# Switch.net
KiCad netlist of a schematic drawn in Altium Designer
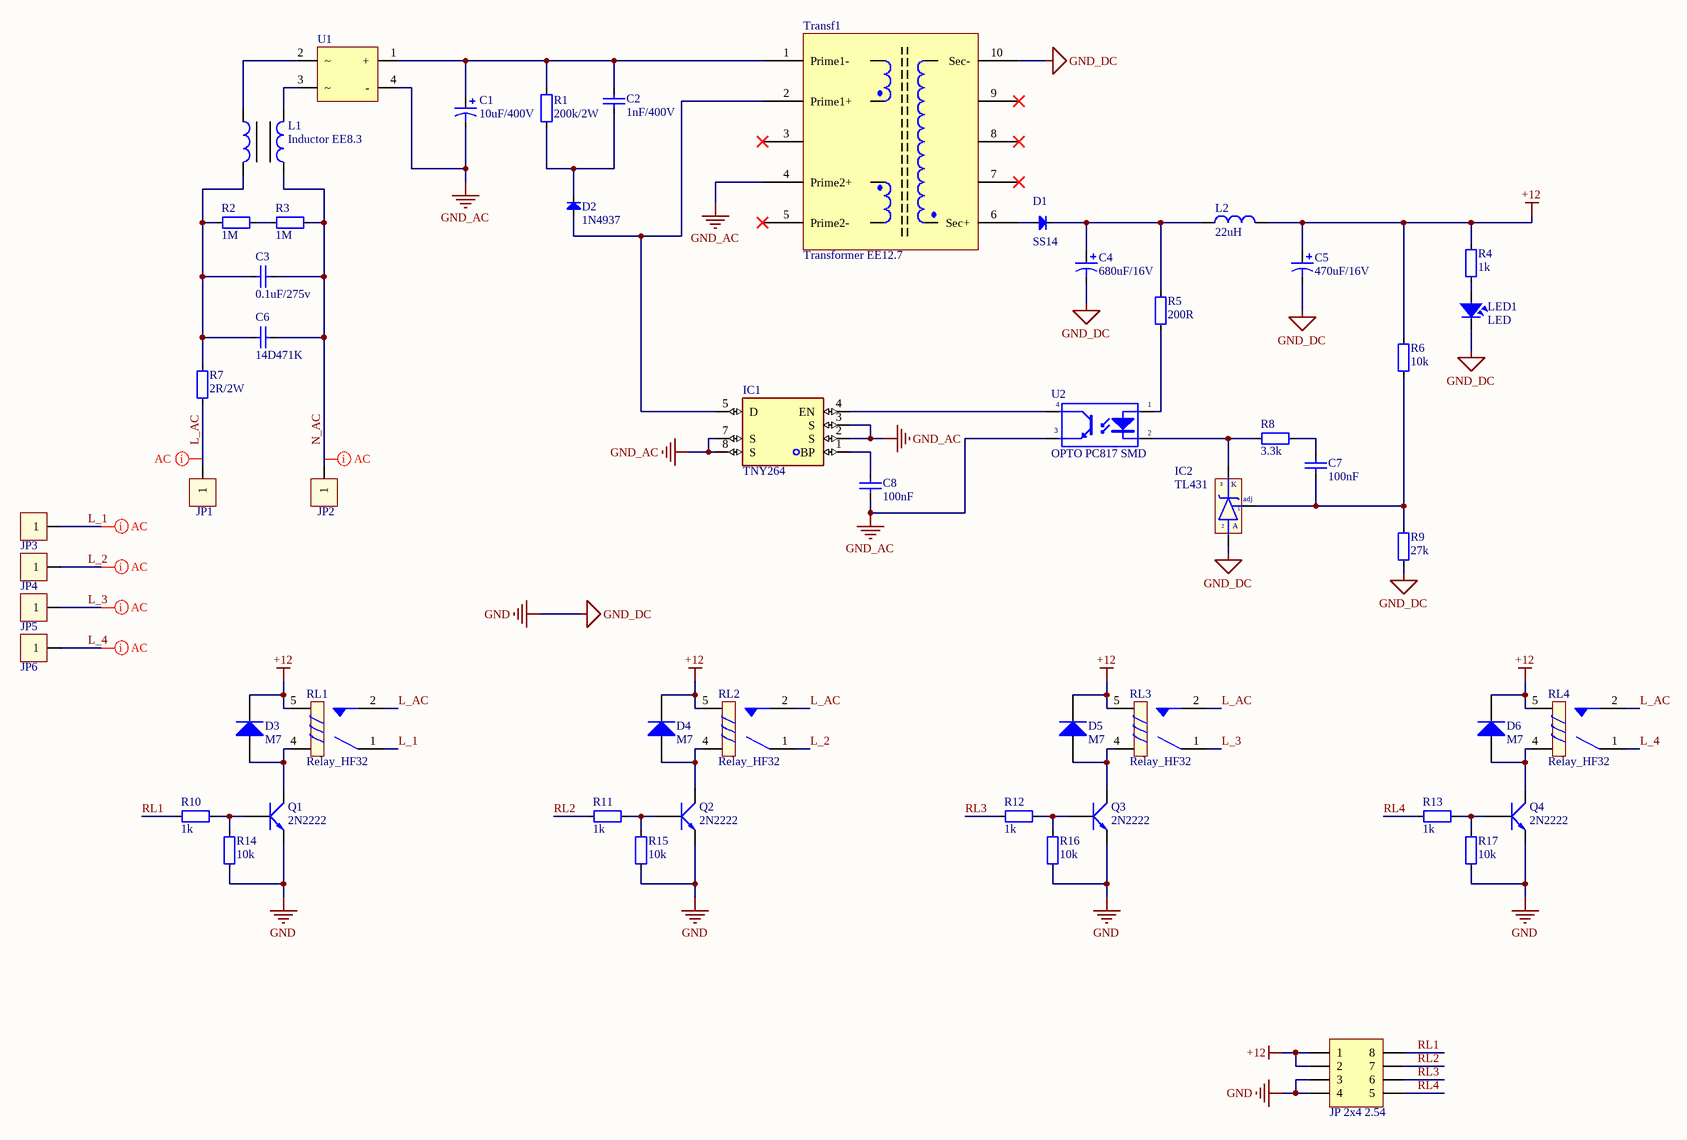
[diagram p0: Switch.SchDoc]

(export (version "E")
  (design (tool "Eeschema 10.0.6"))
  (components
    (comp (ref "C1")
      (value "10uF/400V")
      (footprint "C10mm")
      (description "Polarized Capacitor (Axial)")
      (fields (field (name "PUBLISHER") "Altium Limited"))
      (libsource (lib "My Library") (part "Cap Pol"))
    )
    (comp (ref "C2")
      (value "1nF/400V")
      (footprint "103/2KV")
      (description "CAP CERAMIC")
      (fields (field (name "PUBLISHER") "Altium Limited"))
      (libsource (lib "My Library") (part "Cap2KV"))
    )
    (comp (ref "C3")
      (value "0.1uF/275v")
      (footprint "Cap AC filter")
      (description "Tụ lọc nguồn AC 0.1uf 275v 10mm")
      (libsource (lib "My Library") (part "Cap AC filter"))
    )
    (comp (ref "C4")
      (value "680uF/16V")
      (footprint "C8mm")
      (description "Polarized Capacitor (Axial)")
      (fields (field (name "PUBLISHER") "Altium Limited"))
      (libsource (lib "My Library") (part "Cap Pol"))
    )
    (comp (ref "C5")
      (value "470uF/16V")
      (footprint "C8mm")
      (description "Polarized Capacitor (Axial)")
      (fields (field (name "PUBLISHER") "Altium Limited"))
      (libsource (lib "My Library") (part "Cap Pol"))
    )
    (comp (ref "C6")
      (value "14D471K")
      (footprint "103/2KV")
      (description "Capacitor Ceramic 2KV")
      (fields (field (name "PUBLISHER") "Altium Limited"))
      (libsource (lib "My Library") (part "Cap2KV"))
    )
    (comp (ref "C7")
      (value "100nF")
      (footprint "CAP_0603")
      (description "Capacitor")
      (fields (field (name "PUBLISHER") "Altium Limited"))
      (libsource (lib "My Library") (part "CapSMD"))
    )
    (comp (ref "C8")
      (value "100nF")
      (footprint "CAP_0603")
      (description "Capacitor")
      (fields (field (name "PUBLISHER") "Altium Limited"))
      (libsource (lib "My Library") (part "CapSMD"))
    )
    (comp (ref "D1")
      (value "SS14")
      (footprint "DO-214AC(SMA)")
      (description "Diode Schottky\r\n1N5819")
      (fields (field (name "PUBLISHER") "Altium Limited"))
      (libsource (lib "My Library") (part "Diode SMD"))
    )
    (comp (ref "D2")
      (value "1N4937")
      (footprint "DIO-1AN")
      (description "Diode Schottky\r\n1N4937")
      (fields (field (name "PUBLISHER") "Altium Limited"))
      (libsource (lib "My Library") (part "Diode SMD"))
    )
    (comp (ref "D3")
      (value "M7")
      (footprint "DIODE SMA")
      (description "Dán")
      (libsource (lib "Altium_Lib_by_KhueNguyenCreator") (part "Diode M7 ( 4007 )"))
    )
    (comp (ref "D4")
      (value "M7")
      (footprint "DIODE SMA")
      (description "Dán")
      (libsource (lib "Altium_Lib_by_KhueNguyenCreator") (part "Diode M7 ( 4007 )"))
    )
    (comp (ref "D5")
      (value "M7")
      (footprint "DIODE SMA")
      (description "Dán")
      (libsource (lib "Altium_Lib_by_KhueNguyenCreator") (part "Diode M7 ( 4007 )"))
    )
    (comp (ref "D6")
      (value "M7")
      (footprint "DIODE SMA")
      (description "Dán")
      (libsource (lib "Altium_Lib_by_KhueNguyenCreator") (part "Diode M7 ( 4007 )"))
    )
    (comp (ref "IC1")
      (value "TNY264")
      (footprint "TNY264")
      (description "IC Power")
      (libsource (lib "My Library") (part "TNY264"))
    )
    (comp (ref "IC2")
      (value "TL431")
      (footprint "qto-92")
      (description "Programmable Shunt Regulator")
      (libsource (lib "My Library") (part "TL431"))
    )
    (comp (ref "JP1")
      (value "Coc_dong")
      (footprint "Coc_dong")
      (libsource (lib "My Library") (part "Coc_dong"))
    )
    (comp (ref "JP2")
      (value "Coc_dong")
      (footprint "Coc_dong")
      (libsource (lib "My Library") (part "Coc_dong"))
    )
    (comp (ref "JP3") (value "Coc_dong") (footprint "Coc_dong") (libsource (lib "") (part "Coc_dong_1")))
    (comp (ref "JP4") (value "Coc_dong") (footprint "Coc_dong") (libsource (lib "") (part "Coc_dong_1")))
    (comp (ref "JP5") (value "Coc_dong") (footprint "Coc_dong") (libsource (lib "") (part "Coc_dong_1")))
    (comp (ref "JP6") (value "Coc_dong") (footprint "Coc_dong") (libsource (lib "") (part "Coc_dong_1")))
    (comp (ref "JP7")
      (value "JP 2x4 2.54")
      (footprint "JP 2x4 DT")
      (description "Cắm")
      (libsource (lib "Altium_Lib_by_KhueNguyenCreator") (part "JP 2x4 2.54 Duc Thang"))
    )
    (comp (ref "L1")
      (value "Inductor EE8.3")
      (footprint "Inductor EE8.3")
      (libsource (lib "My Library") (part "Inductor EE8.3"))
    )
    (comp (ref "L2")
      (value "22uH")
      (footprint "L_SMD")
      (description "CD73R 22uH 1.23A 7345")
      (libsource (lib "My Library") (part "Inductor"))
    )
    (comp (ref "LED1")
      (value "LED")
      (footprint "LED-0805-Red")
      (description "LED Single colour Green and Red")
      (libsource (lib "My Library") (part "LED"))
    )
    (comp (ref "Q1")
      (value "2N2222")
      (footprint "SOT23")
      (description "NPN transistor")
      (libsource (lib "Altium_Lib_by_KhueNguyenCreator") (part "C1815 HF SMD"))
    )
    (comp (ref "Q2")
      (value "2N2222")
      (footprint "SOT23")
      (description "NPN transistor")
      (libsource (lib "Altium_Lib_by_KhueNguyenCreator") (part "C1815 HF SMD"))
    )
    (comp (ref "Q3")
      (value "2N2222")
      (footprint "SOT23")
      (description "NPN transistor")
      (libsource (lib "Altium_Lib_by_KhueNguyenCreator") (part "C1815 HF SMD"))
    )
    (comp (ref "Q4")
      (value "2N2222")
      (footprint "SOT23")
      (description "NPN transistor")
      (libsource (lib "Altium_Lib_by_KhueNguyenCreator") (part "C1815 HF SMD"))
    )
    (comp (ref "R1")
      (value "200k/2W")
      (footprint "RES-1WW")
      (description "Resistor")
      (fields
        (field (name "MANUFACTURER") "Generic Components")
        (field (name "PUBLISHER") "Altium Hobart Technology Centre")
      )
      (libsource (lib "My Library") (part "Resistor - SMD"))
    )
    (comp (ref "R2")
      (value "1M")
      (footprint "RES-SMD-1206")
      (description "Resistor")
      (fields
        (field (name "MANUFACTURER") "Generic Components")
        (field (name "PUBLISHER") "Altium Hobart Technology Centre")
      )
      (libsource (lib "My Library") (part "Resistor - SMD"))
    )
    (comp (ref "R3")
      (value "1M")
      (footprint "RES-SMD-1206")
      (description "Resistor")
      (fields
        (field (name "MANUFACTURER") "Generic Components")
        (field (name "PUBLISHER") "Altium Hobart Technology Centre")
      )
      (libsource (lib "My Library") (part "Resistor - SMD"))
    )
    (comp (ref "R4")
      (value "1k")
      (footprint "RES-SMD-0603")
      (description "Resistor")
      (fields
        (field (name "MANUFACTURER") "Generic Components")
        (field (name "PUBLISHER") "Altium Hobart Technology Centre")
      )
      (libsource (lib "My Library") (part "Resistor - SMD"))
    )
    (comp (ref "R5")
      (value "200R")
      (footprint "RES-SMD-0603")
      (description "Resistor")
      (fields
        (field (name "MANUFACTURER") "Generic Components")
        (field (name "PUBLISHER") "Altium Hobart Technology Centre")
      )
      (libsource (lib "My Library") (part "Resistor - SMD"))
    )
    (comp (ref "R6")
      (value "10k")
      (footprint "RES-SMD-0603")
      (description "Resistor")
      (fields
        (field (name "MANUFACTURER") "Generic Components")
        (field (name "PUBLISHER") "Altium Hobart Technology Centre")
      )
      (libsource (lib "My Library") (part "Resistor - SMD"))
    )
    (comp (ref "R7")
      (value "2R/2W")
      (footprint "RES-1WW")
      (description "Resistor")
      (fields
        (field (name "MANUFACTURER") "Generic Components")
        (field (name "PUBLISHER") "Altium Hobart Technology Centre")
      )
      (libsource (lib "My Library") (part "Resistor - SMD"))
    )
    (comp (ref "R8")
      (value "3.3k")
      (footprint "RES-SMD-0603")
      (description "Resistor")
      (fields
        (field (name "MANUFACTURER") "Generic Components")
        (field (name "PUBLISHER") "Altium Hobart Technology Centre")
      )
      (libsource (lib "My Library") (part "Resistor - SMD"))
    )
    (comp (ref "R9")
      (value "27k")
      (footprint "RES-SMD-0603")
      (description "Resistor")
      (fields
        (field (name "MANUFACTURER") "Generic Components")
        (field (name "PUBLISHER") "Altium Hobart Technology Centre")
      )
      (libsource (lib "My Library") (part "Resistor - SMD"))
    )
    (comp (ref "R10")
      (value "1k")
      (footprint "RES-SMD-0603")
      (description "Resistor")
      (fields
        (field (name "MANUFACTURER") "Generic Components")
        (field (name "PUBLISHER") "Altium Hobart Technology Centre")
      )
      (libsource (lib "My Library") (part "Resistor - SMD"))
    )
    (comp (ref "R11")
      (value "1k")
      (footprint "RES-SMD-0603")
      (description "Resistor")
      (fields
        (field (name "MANUFACTURER") "Generic Components")
        (field (name "PUBLISHER") "Altium Hobart Technology Centre")
      )
      (libsource (lib "My Library") (part "Resistor - SMD"))
    )
    (comp (ref "R12")
      (value "1k")
      (footprint "RES-SMD-0603")
      (description "Resistor")
      (fields
        (field (name "MANUFACTURER") "Generic Components")
        (field (name "PUBLISHER") "Altium Hobart Technology Centre")
      )
      (libsource (lib "My Library") (part "Resistor - SMD"))
    )
    (comp (ref "R13")
      (value "1k")
      (footprint "RES-SMD-0603")
      (description "Resistor")
      (fields
        (field (name "MANUFACTURER") "Generic Components")
        (field (name "PUBLISHER") "Altium Hobart Technology Centre")
      )
      (libsource (lib "My Library") (part "Resistor - SMD"))
    )
    (comp (ref "R14")
      (value "10k")
      (footprint "RES-SMD-0603")
      (description "Resistor")
      (fields
        (field (name "MANUFACTURER") "Generic Components")
        (field (name "PUBLISHER") "Altium Hobart Technology Centre")
      )
      (libsource (lib "My Library") (part "Resistor - SMD"))
    )
    (comp (ref "R15")
      (value "10k")
      (footprint "RES-SMD-0603")
      (description "Resistor")
      (fields
        (field (name "MANUFACTURER") "Generic Components")
        (field (name "PUBLISHER") "Altium Hobart Technology Centre")
      )
      (libsource (lib "My Library") (part "Resistor - SMD"))
    )
    (comp (ref "R16")
      (value "10k")
      (footprint "RES-SMD-0603")
      (description "Resistor")
      (fields
        (field (name "MANUFACTURER") "Generic Components")
        (field (name "PUBLISHER") "Altium Hobart Technology Centre")
      )
      (libsource (lib "My Library") (part "Resistor - SMD"))
    )
    (comp (ref "R17")
      (value "10k")
      (footprint "RES-SMD-0603")
      (description "Resistor")
      (fields
        (field (name "MANUFACTURER") "Generic Components")
        (field (name "PUBLISHER") "Altium Hobart Technology Centre")
      )
      (libsource (lib "My Library") (part "Resistor - SMD"))
    )
    (comp (ref "RL1")
      (value "Relay_HF32")
      (footprint "HF32F")
      (libsource (lib "My Library") (part "Relay_HF32"))
    )
    (comp (ref "RL2")
      (value "Relay_HF32")
      (footprint "HF32F")
      (libsource (lib "My Library") (part "Relay_HF32"))
    )
    (comp (ref "RL3")
      (value "Relay_HF32")
      (footprint "HF32F")
      (libsource (lib "My Library") (part "Relay_HF32"))
    )
    (comp (ref "RL4")
      (value "Relay_HF32")
      (footprint "HF32F")
      (libsource (lib "My Library") (part "Relay_HF32"))
    )
    (comp (ref "Transf1")
      (value "Transformer EE12.7")
      (footprint "Transformer EE12.7")
      (libsource (lib "My Library") (part "Tranformer EE16"))
    )
    (comp (ref "U1")
      (value "Diode Bridge Flate")
      (footprint "DB207S")
      (description "Diode Bridge")
      (libsource (lib "My Library") (part "Diode Bridge Flate"))
    )
    (comp (ref "U2")
      (value "OPTO PC817 SMD")
      (footprint "SOP4")
      (description "Single Opto")
      (libsource (lib "Altium_Lib_by_KhueNguyenCreator") (part "OPTO PC817 SMD"))
    )
  )
  (nets
    (net (code "1") (name "+12") (class "Default")
      (node (ref "C5") (pin "1") (pinfunction "1_1") (pintype "passive"))
      (node (ref "D3") (pin "2") (pinfunction "K_2") (pintype "passive"))
      (node (ref "D4") (pin "2") (pinfunction "K_2") (pintype "passive"))
      (node (ref "D5") (pin "2") (pinfunction "K_2") (pintype "passive"))
      (node (ref "D6") (pin "2") (pinfunction "K_2") (pintype "passive"))
      (node (ref "JP7") (pin "1") (pinfunction "1_1") (pintype "passive"))
      (node (ref "JP7") (pin "2") (pinfunction "2_2") (pintype "passive"))
      (node (ref "L2") (pin "2") (pinfunction "2_2") (pintype "passive"))
      (node (ref "R4") (pin "2") (pinfunction "2_2") (pintype "passive"))
      (node (ref "R6") (pin "2") (pinfunction "2_2") (pintype "passive"))
      (node (ref "RL1") (pin "5") (pinfunction "5_5") (pintype "passive"))
      (node (ref "RL2") (pin "5") (pinfunction "5_5") (pintype "passive"))
      (node (ref "RL3") (pin "5") (pinfunction "5_5") (pintype "passive"))
      (node (ref "RL4") (pin "5") (pinfunction "5_5") (pintype "passive"))
    )
    (net (code "2") (name "/L_1") (class "Default")
      (node (ref "JP3") (pin "1") (pinfunction "1_1") (pintype "passive"))
      (node (ref "RL1") (pin "1") (pinfunction "1_1") (pintype "passive"))
    )
    (net (code "3") (name "/L_2") (class "Default")
      (node (ref "JP4") (pin "1") (pinfunction "1_1") (pintype "passive"))
      (node (ref "RL2") (pin "1") (pinfunction "1_1") (pintype "passive"))
    )
    (net (code "4") (name "/L_3") (class "Default")
      (node (ref "JP5") (pin "1") (pinfunction "1_1") (pintype "passive"))
      (node (ref "RL3") (pin "1") (pinfunction "1_1") (pintype "passive"))
    )
    (net (code "5") (name "/L_4") (class "Default")
      (node (ref "JP6") (pin "1") (pinfunction "1_1") (pintype "passive"))
      (node (ref "RL4") (pin "1") (pinfunction "1_1") (pintype "passive"))
    )
    (net (code "6") (name "/L_AC") (class "Default")
      (node (ref "JP1") (pin "1") (pinfunction "1_1") (pintype "passive"))
      (node (ref "R7") (pin "1") (pinfunction "1_1") (pintype "passive"))
      (node (ref "RL1") (pin "2") (pinfunction "2_2") (pintype "passive"))
      (node (ref "RL2") (pin "2") (pinfunction "2_2") (pintype "passive"))
      (node (ref "RL3") (pin "2") (pinfunction "2_2") (pintype "passive"))
      (node (ref "RL4") (pin "2") (pinfunction "2_2") (pintype "passive"))
    )
    (net (code "7") (name "/N_AC") (class "Default")
      (node (ref "C3") (pin "1") (pinfunction "1_1") (pintype "passive"))
      (node (ref "C6") (pin "1") (pinfunction "1_1") (pintype "passive"))
      (node (ref "JP2") (pin "1") (pinfunction "1_1") (pintype "passive"))
      (node (ref "L1") (pin "1") (pinfunction "1_1") (pintype "passive"))
      (node (ref "R3") (pin "1") (pinfunction "1_1") (pintype "passive"))
    )
    (net (code "8") (name "/RL1") (class "Default")
      (node (ref "JP7") (pin "8") (pinfunction "8_8") (pintype "passive"))
      (node (ref "R10") (pin "1") (pinfunction "1_1") (pintype "passive"))
    )
    (net (code "9") (name "/RL2") (class "Default")
      (node (ref "JP7") (pin "7") (pinfunction "7_7") (pintype "passive"))
      (node (ref "R11") (pin "1") (pinfunction "1_1") (pintype "passive"))
    )
    (net (code "10") (name "/RL3") (class "Default")
      (node (ref "JP7") (pin "6") (pinfunction "6_6") (pintype "passive"))
      (node (ref "R12") (pin "1") (pinfunction "1_1") (pintype "passive"))
    )
    (net (code "11") (name "/RL4") (class "Default")
      (node (ref "JP7") (pin "5") (pinfunction "5_5") (pintype "passive"))
      (node (ref "R13") (pin "1") (pinfunction "1_1") (pintype "passive"))
    )
    (net (code "12") (name "GND") (class "Default")
      (node (ref "C4") (pin "2") (pinfunction "2_2") (pintype "passive"))
      (node (ref "C5") (pin "2") (pinfunction "2_2") (pintype "passive"))
      (node (ref "IC2") (pin "2") (pinfunction "A_2") (pintype "passive"))
      (node (ref "JP7") (pin "3") (pinfunction "3_3") (pintype "passive"))
      (node (ref "JP7") (pin "4") (pinfunction "4_4") (pintype "passive"))
      (node (ref "LED1") (pin "2") (pinfunction "2_2") (pintype "passive"))
      (node (ref "Q1") (pin "2") (pinfunction "E_2") (pintype "passive"))
      (node (ref "Q2") (pin "2") (pinfunction "E_2") (pintype "passive"))
      (node (ref "Q3") (pin "2") (pinfunction "E_2") (pintype "passive"))
      (node (ref "Q4") (pin "2") (pinfunction "E_2") (pintype "passive"))
      (node (ref "R14") (pin "1") (pinfunction "1_1") (pintype "passive"))
      (node (ref "R15") (pin "1") (pinfunction "1_1") (pintype "passive"))
      (node (ref "R16") (pin "1") (pinfunction "1_1") (pintype "passive"))
      (node (ref "R17") (pin "1") (pinfunction "1_1") (pintype "passive"))
      (node (ref "R9") (pin "1") (pinfunction "1_1") (pintype "passive"))
      (node (ref "Transf1") (pin "10") (pinfunction "Sec-_10") (pintype "passive"))
    )
    (net (code "13") (name "GND_AC") (class "Default")
      (node (ref "C1") (pin "2") (pinfunction "2_2") (pintype "passive"))
      (node (ref "C8") (pin "1") (pinfunction "1_1") (pintype "passive"))
      (node (ref "IC1") (pin "2") (pinfunction "S_2") (pintype "bidirectional"))
      (node (ref "IC1") (pin "3") (pinfunction "S_3") (pintype "bidirectional"))
      (node (ref "IC1") (pin "7") (pinfunction "S_7") (pintype "bidirectional"))
      (node (ref "IC1") (pin "8") (pinfunction "S_8") (pintype "bidirectional"))
      (node (ref "Transf1") (pin "4") (pinfunction "Prime2+_4") (pintype "passive"))
      (node (ref "U1") (pin "4") (pinfunction "-_4") (pintype "passive"))
      (node (ref "U2") (pin "3") (pinfunction "E_3") (pintype "passive"))
    )
    (net (code "14") (name "Net-(C3-Pad2)") (class "Default")
      (node (ref "C3") (pin "2") (pinfunction "2_2") (pintype "passive"))
      (node (ref "C6") (pin "2") (pinfunction "2_2") (pintype "passive"))
      (node (ref "L1") (pin "3") (pinfunction "3_3") (pintype "passive"))
      (node (ref "R2") (pin "2") (pinfunction "2_2") (pintype "passive"))
      (node (ref "R7") (pin "2") (pinfunction "2_2") (pintype "passive"))
    )
    (net (code "15") (name "Net-(C7-Pad2)") (class "Default")
      (node (ref "C7") (pin "2") (pinfunction "2_2") (pintype "passive"))
      (node (ref "R8") (pin "1") (pinfunction "1_1") (pintype "passive"))
    )
    (net (code "16") (name "Net-(D1-A)") (class "Default")
      (node (ref "D1") (pin "1") (pinfunction "A_1") (pintype "passive"))
      (node (ref "Transf1") (pin "6") (pinfunction "Sec+_6") (pintype "passive"))
    )
    (net (code "17") (name "Net-(D1-K)") (class "Default")
      (node (ref "C4") (pin "1") (pinfunction "1_1") (pintype "passive"))
      (node (ref "D1") (pin "2") (pinfunction "K_2") (pintype "passive"))
      (node (ref "L2") (pin "1") (pinfunction "1_1") (pintype "passive"))
      (node (ref "R5") (pin "2") (pinfunction "2_2") (pintype "passive"))
    )
    (net (code "18") (name "Net-(D2-A)") (class "Default")
      (node (ref "D2") (pin "1") (pinfunction "A_1") (pintype "passive"))
      (node (ref "IC1") (pin "5") (pinfunction "D_5") (pintype "bidirectional"))
      (node (ref "Transf1") (pin "2") (pinfunction "Prime1+_2") (pintype "passive"))
    )
    (net (code "19") (name "Net-(D2-K)") (class "Default")
      (node (ref "C2") (pin "2") (pinfunction "2_2") (pintype "passive"))
      (node (ref "D2") (pin "2") (pinfunction "K_2") (pintype "passive"))
      (node (ref "R1") (pin "1") (pinfunction "1_1") (pintype "passive"))
    )
    (net (code "20") (name "Net-(D3-A)") (class "Default")
      (node (ref "D3") (pin "1") (pinfunction "A_1") (pintype "passive"))
      (node (ref "Q1") (pin "3") (pinfunction "C_3") (pintype "passive"))
      (node (ref "RL1") (pin "4") (pinfunction "4_4") (pintype "passive"))
    )
    (net (code "21") (name "Net-(D4-A)") (class "Default")
      (node (ref "D4") (pin "1") (pinfunction "A_1") (pintype "passive"))
      (node (ref "Q2") (pin "3") (pinfunction "C_3") (pintype "passive"))
      (node (ref "RL2") (pin "4") (pinfunction "4_4") (pintype "passive"))
    )
    (net (code "22") (name "Net-(D5-A)") (class "Default")
      (node (ref "D5") (pin "1") (pinfunction "A_1") (pintype "passive"))
      (node (ref "Q3") (pin "3") (pinfunction "C_3") (pintype "passive"))
      (node (ref "RL3") (pin "4") (pinfunction "4_4") (pintype "passive"))
    )
    (net (code "23") (name "Net-(D6-A)") (class "Default")
      (node (ref "D6") (pin "1") (pinfunction "A_1") (pintype "passive"))
      (node (ref "Q4") (pin "3") (pinfunction "C_3") (pintype "passive"))
      (node (ref "RL4") (pin "4") (pinfunction "4_4") (pintype "passive"))
    )
    (net (code "24") (name "Net-(IC1-BP)") (class "Default")
      (node (ref "C8") (pin "2") (pinfunction "2_2") (pintype "passive"))
      (node (ref "IC1") (pin "1") (pinfunction "BP_1") (pintype "bidirectional"))
    )
    (net (code "25") (name "Net-(IC1-EN)") (class "Default")
      (node (ref "IC1") (pin "4") (pinfunction "EN_4") (pintype "bidirectional"))
      (node (ref "U2") (pin "4") (pinfunction "C_4") (pintype "passive"))
    )
    (net (code "26") (name "Net-(IC2-K)") (class "Default")
      (node (ref "IC2") (pin "3") (pinfunction "K_3") (pintype "passive"))
      (node (ref "R8") (pin "2") (pinfunction "2_2") (pintype "passive"))
      (node (ref "U2") (pin "2") (pinfunction "K_2") (pintype "passive"))
    )
    (net (code "27") (name "Net-(IC2-adj)") (class "Default")
      (node (ref "C7") (pin "1") (pinfunction "1_1") (pintype "passive"))
      (node (ref "IC2") (pin "1") (pinfunction "adj_1") (pintype "passive"))
      (node (ref "R6") (pin "1") (pinfunction "1_1") (pintype "passive"))
      (node (ref "R9") (pin "2") (pinfunction "2_2") (pintype "passive"))
    )
    (net (code "28") (name "Net-(L1-Pad2)") (class "Default")
      (node (ref "L1") (pin "2") (pinfunction "2_2") (pintype "passive"))
      (node (ref "U1") (pin "3") (pinfunction "~_3") (pintype "passive"))
    )
    (net (code "29") (name "Net-(L1-Pad4)") (class "Default")
      (node (ref "L1") (pin "4") (pinfunction "4_4") (pintype "passive"))
      (node (ref "U1") (pin "2") (pinfunction "~_2") (pintype "passive"))
    )
    (net (code "30") (name "Net-(LED1-Pad1)") (class "Default")
      (node (ref "LED1") (pin "1") (pinfunction "1_1") (pintype "passive"))
      (node (ref "R4") (pin "1") (pinfunction "1_1") (pintype "passive"))
    )
    (net (code "31") (name "Net-(Q1-B)") (class "Default")
      (node (ref "Q1") (pin "1") (pinfunction "B_1") (pintype "passive"))
      (node (ref "R10") (pin "2") (pinfunction "2_2") (pintype "passive"))
      (node (ref "R14") (pin "2") (pinfunction "2_2") (pintype "passive"))
    )
    (net (code "32") (name "Net-(Q2-B)") (class "Default")
      (node (ref "Q2") (pin "1") (pinfunction "B_1") (pintype "passive"))
      (node (ref "R11") (pin "2") (pinfunction "2_2") (pintype "passive"))
      (node (ref "R15") (pin "2") (pinfunction "2_2") (pintype "passive"))
    )
    (net (code "33") (name "Net-(Q3-B)") (class "Default")
      (node (ref "Q3") (pin "1") (pinfunction "B_1") (pintype "passive"))
      (node (ref "R12") (pin "2") (pinfunction "2_2") (pintype "passive"))
      (node (ref "R16") (pin "2") (pinfunction "2_2") (pintype "passive"))
    )
    (net (code "34") (name "Net-(Q4-B)") (class "Default")
      (node (ref "Q4") (pin "1") (pinfunction "B_1") (pintype "passive"))
      (node (ref "R13") (pin "2") (pinfunction "2_2") (pintype "passive"))
      (node (ref "R17") (pin "2") (pinfunction "2_2") (pintype "passive"))
    )
    (net (code "35") (name "Net-(R2-Pad1)") (class "Default")
      (node (ref "R2") (pin "1") (pinfunction "1_1") (pintype "passive"))
      (node (ref "R3") (pin "2") (pinfunction "2_2") (pintype "passive"))
    )
    (net (code "36") (name "Net-(Transf1-Prime1-)") (class "Default")
      (node (ref "C1") (pin "1") (pinfunction "1_1") (pintype "passive"))
      (node (ref "C2") (pin "1") (pinfunction "1_1") (pintype "passive"))
      (node (ref "R1") (pin "2") (pinfunction "2_2") (pintype "passive"))
      (node (ref "Transf1") (pin "1") (pinfunction "Prime1-_1") (pintype "passive"))
      (node (ref "U1") (pin "1") (pinfunction "+_1") (pintype "passive"))
    )
    (net (code "37") (name "Net-(U2-A)") (class "Default")
      (node (ref "R5") (pin "1") (pinfunction "1_1") (pintype "passive"))
      (node (ref "U2") (pin "1") (pinfunction "A_1") (pintype "passive"))
    )
    (net (code "38") (name "unconnected-(Transf1-Pad3)") (class "Default")
      (node (ref "Transf1") (pin "3") (pintype "passive+no_connect"))
    )
    (net (code "39") (name "unconnected-(Transf1-Pad7)") (class "Default")
      (node (ref "Transf1") (pin "7") (pintype "passive+no_connect"))
    )
    (net (code "40") (name "unconnected-(Transf1-Pad8)") (class "Default")
      (node (ref "Transf1") (pin "8") (pintype "passive+no_connect"))
    )
    (net (code "41") (name "unconnected-(Transf1-Pad9)") (class "Default")
      (node (ref "Transf1") (pin "9") (pintype "passive+no_connect"))
    )
    (net (code "42") (name "unconnected-(Transf1-Prime2--Pad5)") (class "Default")
      (node (ref "Transf1") (pin "5") (pinfunction "Prime2-_5") (pintype "passive+no_connect"))
    )
  )
)
